# T02_noclock_rev1.net
KiCad netlist of a schematic drawn in EAGLE
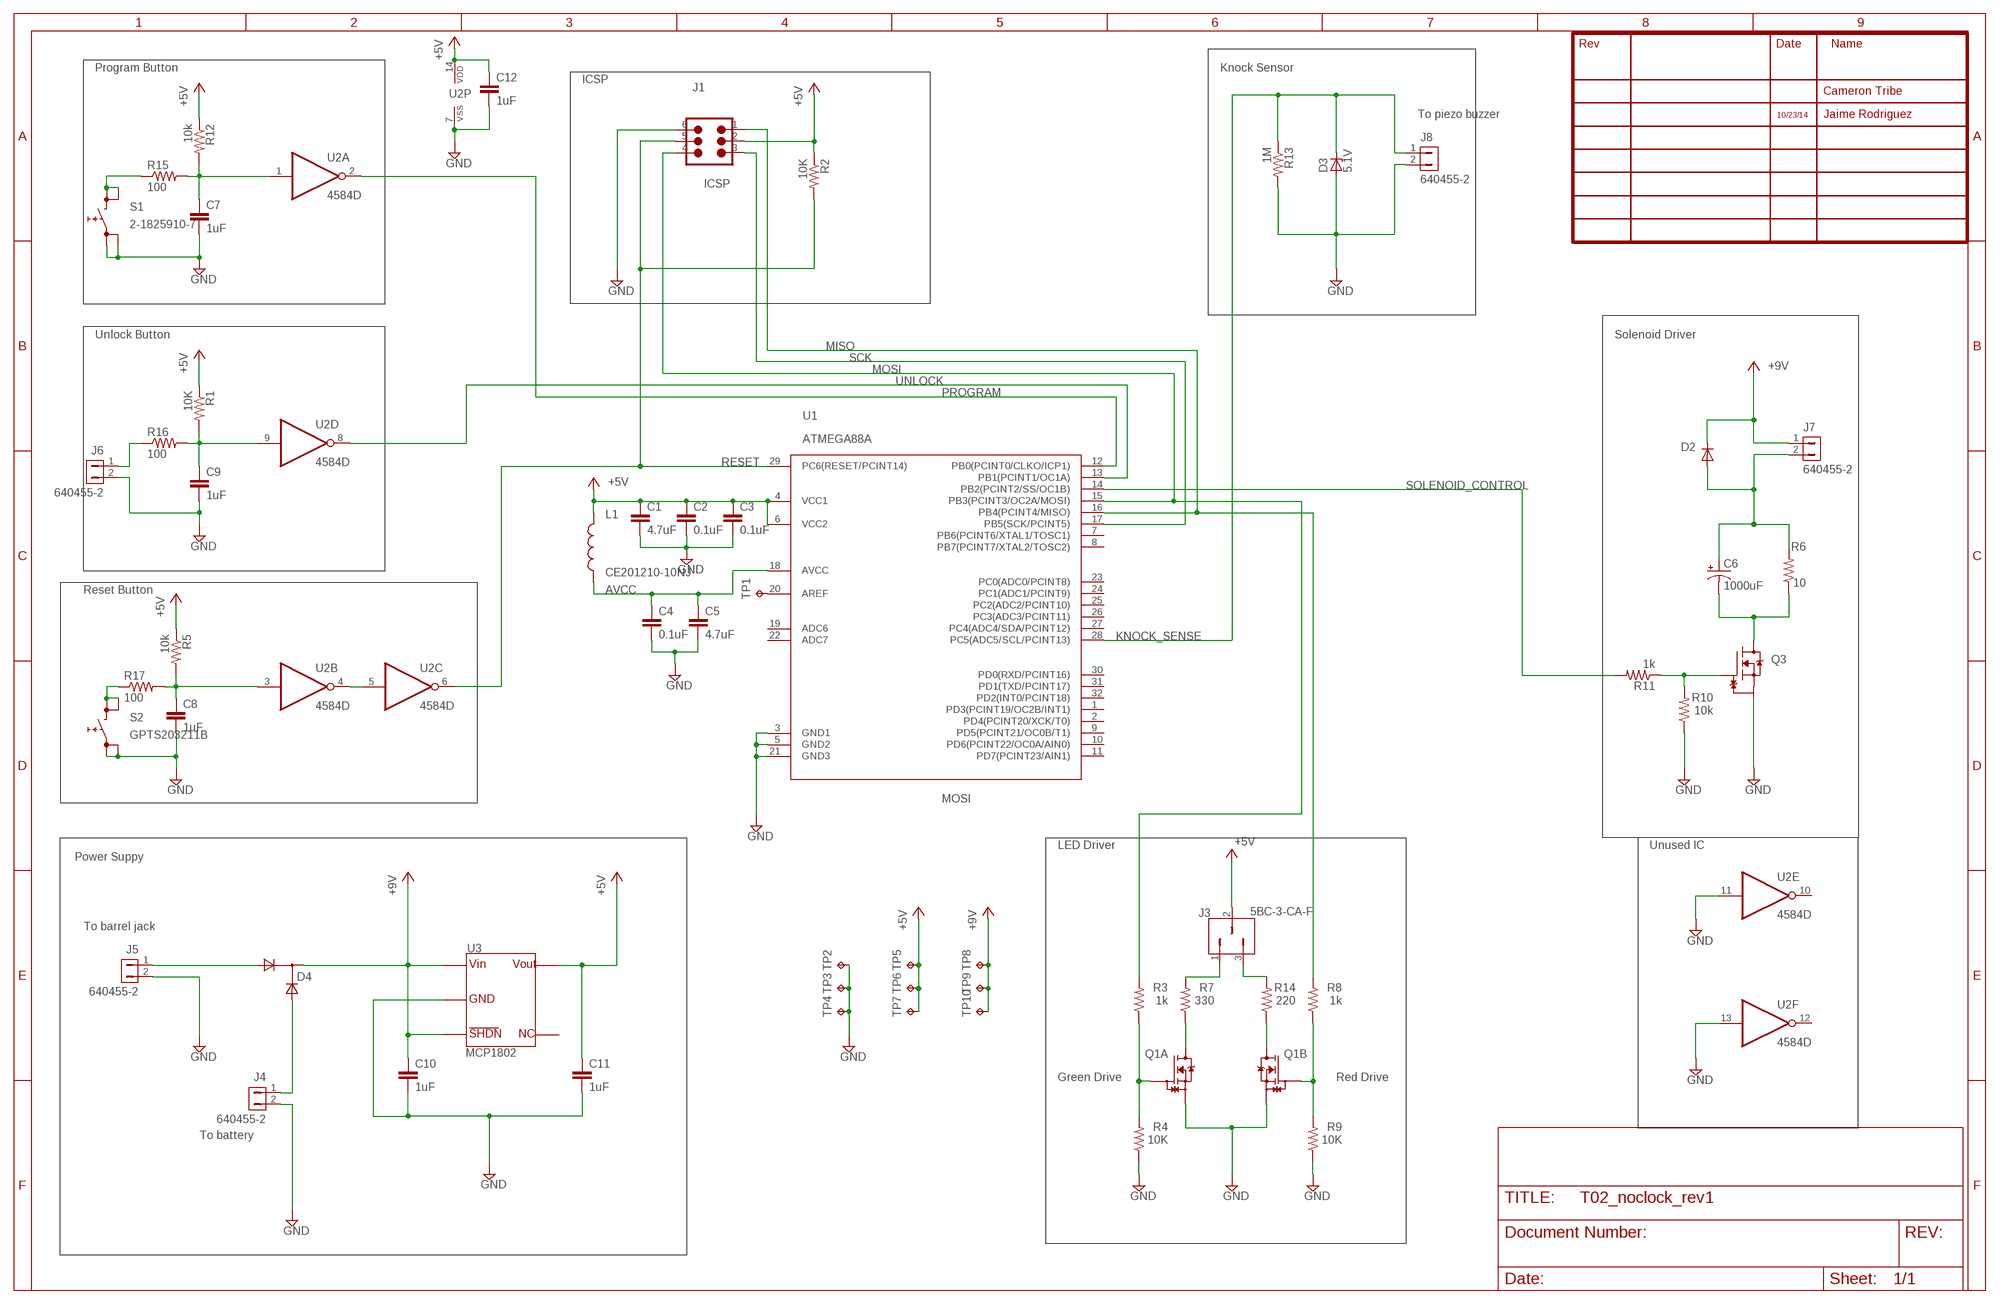
[diagram p0: schematic, sheet 1]

(export (version "E")
  (design (tool "Eeschema 10.0.6"))
  (components
    (comp (ref "C1")
      (value "4.7uF")
      (footprint "eagle-import:C0805")
      (fields (field (name "PARTNUM") "CL21A475KOFNNNE"))
      (libsource (lib "eagle-import") (part "C-EUC0805"))
    )
    (comp (ref "C2")
      (value "0.1uF")
      (footprint "eagle-import:C0805")
      (fields (field (name "PARTNUM") "GRM155R61A104KA01D"))
      (libsource (lib "eagle-import") (part "C-EUC0805"))
    )
    (comp (ref "C3")
      (value "0.1uF")
      (footprint "eagle-import:C0805")
      (fields (field (name "PARTNUM") "GRM155R61A104KA01D"))
      (libsource (lib "eagle-import") (part "C-EUC0805"))
    )
    (comp (ref "C4")
      (value "0.1uF")
      (footprint "eagle-import:C0805")
      (fields (field (name "PARTNUM") "GRM155R61A104KA01D"))
      (libsource (lib "eagle-import") (part "C-EUC0805"))
    )
    (comp (ref "C5")
      (value "4.7uF")
      (footprint "eagle-import:C0805")
      (fields (field (name "PARTNUM") "CL21A475KOFNNNE"))
      (libsource (lib "eagle-import") (part "C-EUC0805"))
    )
    (comp (ref "C6")
      (value "1000uF")
      (footprint "eagle-import:EKY-100ELL102MH20D")
      (libsource (lib "eagle-import") (part "EKY-100ELL102MH20D"))
    )
    (comp (ref "C7")
      (value "1uF")
      (footprint "eagle-import:C0805")
      (fields (field (name "PARTNUM") "CL21B105KBFNNNE"))
      (libsource (lib "eagle-import") (part "C-EUC0805"))
    )
    (comp (ref "C8")
      (value "1uF")
      (footprint "eagle-import:C0805")
      (fields (field (name "PARTNUM") "CL21B105KBFNNNE"))
      (libsource (lib "eagle-import") (part "C-EUC0805"))
    )
    (comp (ref "C9")
      (value "1uF")
      (footprint "eagle-import:C0805")
      (fields (field (name "PARTNUM") "CL21B105KBFNNNE"))
      (libsource (lib "eagle-import") (part "C-EUC0805"))
    )
    (comp (ref "C10")
      (value "1uF")
      (footprint "eagle-import:C0805")
      (fields (field (name "PARTNUM") "CL21B105KBFNNNE"))
      (libsource (lib "eagle-import") (part "C-EUC0805"))
    )
    (comp (ref "C11")
      (value "1uF")
      (footprint "eagle-import:C0805")
      (fields (field (name "PARTNUM") "CL21B105KBFNNNE"))
      (libsource (lib "eagle-import") (part "C-EUC0805"))
    )
    (comp (ref "C12")
      (value "1uF")
      (footprint "eagle-import:C0805")
      (fields (field (name "PARTNUM") "CL21B105KBFNNNE"))
      (libsource (lib "eagle-import") (part "C-EUC0805"))
    )
    (comp (ref "D2")
      (value "GF1")
      (footprint "eagle-import:SMA-DO214AC")
      (fields (field (name "PARTNUM") "S1J"))
      (libsource (lib "eagle-import") (part "GF1"))
    )
    (comp (ref "D3")
      (value "5.1V")
      (footprint "eagle-import:SOT23")
      (fields (field (name "PARTNUM") "BZX84C4V7-TP "))
      (libsource (lib "eagle-import") (part "ZENER-DIODESOT23"))
    )
    (comp (ref "D4")
      (value "PMEG2005CT,215")
      (footprint "eagle-import:SOT-23")
      (libsource (lib "eagle-import") (part "PMEG2005CT,215"))
    )
    (comp (ref "J1")
      (value "ICSP")
      (footprint "eagle-import:ICSP")
      (libsource (lib "eagle-import") (part "ICSP"))
    )
    (comp (ref "J3")
      (value "5BC-3-CA-F")
      (footprint "eagle-import:3_PIN_CONNECTOR")
      (libsource (lib "eagle-import") (part "5BC-3-CA-F"))
    )
    (comp (ref "J4")
      (value "640455-2")
      (footprint "eagle-import:2-PIN_CONNECTOR")
      (libsource (lib "eagle-import") (part "640455-2"))
    )
    (comp (ref "J5")
      (value "640455-2")
      (footprint "eagle-import:2-PIN_CONNECTOR")
      (libsource (lib "eagle-import") (part "640455-2"))
    )
    (comp (ref "J6")
      (value "640455-2")
      (footprint "eagle-import:2-PIN_CONNECTOR")
      (libsource (lib "eagle-import") (part "640455-2"))
    )
    (comp (ref "J7")
      (value "640455-2")
      (footprint "eagle-import:2-PIN_CONNECTOR")
      (libsource (lib "eagle-import") (part "640455-2"))
    )
    (comp (ref "J8")
      (value "640455-2")
      (footprint "eagle-import:2-PIN_CONNECTOR")
      (libsource (lib "eagle-import") (part "640455-2"))
    )
    (comp (ref "L1")
      (value "CE201210-10NJ")
      (footprint "eagle-import:R0805")
      (libsource (lib "eagle-import") (part "CE201210-10NJ"))
    )
    (comp (ref "Q1")
      (value "DMN63D8LDW-7")
      (footprint "eagle-import:SOT363")
      (fields (field (name "PARTNUM") "DMN63D8LDW-7"))
      (libsource (lib "eagle-import") (part "DMN63D8LDW-7"))
    )
    (comp (ref "Q3")
      (value "DMG1012UW-7")
      (footprint "eagle-import:SOT323")
      (libsource (lib "eagle-import") (part "DMG1012UW-7"))
    )
    (comp (ref "R1")
      (value "10K")
      (footprint "eagle-import:R0805")
      (fields (field (name "PARTNUM") "ESR10EZPJ103"))
      (libsource (lib "eagle-import") (part "R-US_R0805"))
    )
    (comp (ref "R2")
      (value "10K")
      (footprint "eagle-import:R0805")
      (fields (field (name "PARTNUM") "ESR10EZPJ103"))
      (libsource (lib "eagle-import") (part "R-US_R0805"))
    )
    (comp (ref "R3")
      (value "1k")
      (footprint "eagle-import:R0805")
      (fields (field (name "PARTNUM") "MCR10ERTF1001"))
      (libsource (lib "eagle-import") (part "R-US_R0805"))
    )
    (comp (ref "R4")
      (value "10K")
      (footprint "eagle-import:R0805")
      (fields (field (name "PARTNUM") "ESR10EZPJ103"))
      (libsource (lib "eagle-import") (part "R-US_R0805"))
    )
    (comp (ref "R5")
      (value "10k")
      (footprint "eagle-import:R0805")
      (fields (field (name "PARTNUM") "ESR10EZPJ103"))
      (libsource (lib "eagle-import") (part "R-US_R0805"))
    )
    (comp (ref "R6")
      (value "10")
      (footprint "eagle-import:R2512")
      (fields (field (name "PARTNUM") "CRM2512-JW-100ELF "))
      (libsource (lib "eagle-import") (part "R-US_R2512"))
    )
    (comp (ref "R7")
      (value "330")
      (footprint "eagle-import:R0805")
      (fields (field (name "PARTNUM") "MCR10ERTF3300"))
      (libsource (lib "eagle-import") (part "R-US_R0805"))
    )
    (comp (ref "R8")
      (value "1k")
      (footprint "eagle-import:R0805")
      (fields (field (name "PARTNUM") "MCR10ERTF1001"))
      (libsource (lib "eagle-import") (part "R-US_R0805"))
    )
    (comp (ref "R9")
      (value "10K")
      (footprint "eagle-import:R0805")
      (fields (field (name "PARTNUM") "ESR10EZPJ103"))
      (libsource (lib "eagle-import") (part "R-US_R0805"))
    )
    (comp (ref "R10")
      (value "10k")
      (footprint "eagle-import:R0805")
      (fields (field (name "PARTNUM") "ESR10EZPJ103"))
      (libsource (lib "eagle-import") (part "R-US_R0805"))
    )
    (comp (ref "R11")
      (value "1k")
      (footprint "eagle-import:R0805")
      (fields (field (name "PARTNUM") "MCR10ERTF1001"))
      (libsource (lib "eagle-import") (part "R-US_R0805"))
    )
    (comp (ref "R12")
      (value "10k")
      (footprint "eagle-import:R0805")
      (fields (field (name "PARTNUM") "ESR10EZPJ103"))
      (libsource (lib "eagle-import") (part "R-US_R0805"))
    )
    (comp (ref "R13")
      (value "1M")
      (footprint "eagle-import:R0805")
      (fields (field (name "PARTNUM") "RMCF0805JT1M00"))
      (libsource (lib "eagle-import") (part "R-US_R0805"))
    )
    (comp (ref "R14")
      (value "220")
      (footprint "eagle-import:R0805")
      (fields (field (name "PARTNUM") "RMCF0805FT220R"))
      (libsource (lib "eagle-import") (part "R-US_R0805"))
    )
    (comp (ref "R15")
      (value "100")
      (footprint "eagle-import:R0805")
      (fields (field (name "PARTNUM") "ESR10EZPJ103"))
      (libsource (lib "eagle-import") (part "R-US_R0805"))
    )
    (comp (ref "R16")
      (value "100")
      (footprint "eagle-import:R0805")
      (fields (field (name "PARTNUM") "ESR10EZPJ103"))
      (libsource (lib "eagle-import") (part "R-US_R0805"))
    )
    (comp (ref "R17")
      (value "100")
      (footprint "eagle-import:R0805")
      (fields (field (name "PARTNUM") "ESR10EZPJ103"))
      (libsource (lib "eagle-import") (part "R-US_R0805"))
    )
    (comp (ref "S1")
      (value "2-1825910-7")
      (footprint "eagle-import:FSM14JH")
      (libsource (lib "eagle-import") (part "2-1825910-7"))
    )
    (comp (ref "S2")
      (value "GPTS203211B")
      (footprint "eagle-import:GPTS203211B")
      (libsource (lib "eagle-import") (part "GPTS203211B"))
    )
    (comp (ref "TP1")
      (value "TPTP19R")
      (footprint "eagle-import:TP19R")
      (libsource (lib "eagle-import") (part "TPTP19R"))
    )
    (comp (ref "TP2")
      (value "TPTP19R")
      (footprint "eagle-import:TP19R")
      (libsource (lib "eagle-import") (part "TPTP19R"))
    )
    (comp (ref "TP3")
      (value "TPTP19R")
      (footprint "eagle-import:TP19R")
      (libsource (lib "eagle-import") (part "TPTP19R"))
    )
    (comp (ref "TP4")
      (value "TPTP19R")
      (footprint "eagle-import:TP19R")
      (libsource (lib "eagle-import") (part "TPTP19R"))
    )
    (comp (ref "TP5")
      (value "TPTP19R")
      (footprint "eagle-import:TP19R")
      (libsource (lib "eagle-import") (part "TPTP19R"))
    )
    (comp (ref "TP6")
      (value "TPTP19R")
      (footprint "eagle-import:TP19R")
      (libsource (lib "eagle-import") (part "TPTP19R"))
    )
    (comp (ref "TP7")
      (value "TPTP19R")
      (footprint "eagle-import:TP19R")
      (libsource (lib "eagle-import") (part "TPTP19R"))
    )
    (comp (ref "TP8")
      (value "TPTP19R")
      (footprint "eagle-import:TP19R")
      (libsource (lib "eagle-import") (part "TPTP19R"))
    )
    (comp (ref "TP9")
      (value "TPTP19R")
      (footprint "eagle-import:TP19R")
      (libsource (lib "eagle-import") (part "TPTP19R"))
    )
    (comp (ref "TP10")
      (value "TPTP19R")
      (footprint "eagle-import:TP19R")
      (libsource (lib "eagle-import") (part "TPTP19R"))
    )
    (comp (ref "U1")
      (value "ATMEGA88A")
      (footprint "eagle-import:TQFP32")
      (fields (field (name "PARTNUM") "ATMEGA88A-AUR "))
      (libsource (lib "eagle-import") (part "ATMEGA88A"))
    )
    (comp (ref "U2")
      (value "4584D")
      (footprint "eagle-import:SO14")
      (fields (field (name "PARTNUM") "4584D"))
      (libsource (lib "eagle-import") (part "4584D"))
    )
    (comp (ref "U3")
      (value "MCP1802")
      (footprint "eagle-import:SOT23-5")
      (libsource (lib "eagle-import") (part "MCP1802"))
    )
  )
  (nets
    (net (code "1") (name "+5V") (class "Default")
      (node (ref "C1") (pin "1") (pinfunction "1_1") (pintype "passive"))
      (node (ref "C11") (pin "1") (pinfunction "1_1") (pintype "passive"))
      (node (ref "C12") (pin "1") (pinfunction "1_1") (pintype "passive"))
      (node (ref "C2") (pin "1") (pinfunction "1_1") (pintype "passive"))
      (node (ref "C3") (pin "1") (pinfunction "1_1") (pintype "passive"))
      (node (ref "J1") (pin "2") (pinfunction "2_2") (pintype "passive"))
      (node (ref "J3") (pin "2") (pinfunction "2_2") (pintype "passive"))
      (node (ref "L1") (pin "2") (pinfunction "2_2") (pintype "passive"))
      (node (ref "R1") (pin "1") (pinfunction "1_1") (pintype "passive"))
      (node (ref "R12") (pin "1") (pinfunction "1_1") (pintype "passive"))
      (node (ref "R2") (pin "1") (pinfunction "1_1") (pintype "passive"))
      (node (ref "R5") (pin "1") (pinfunction "1_1") (pintype "passive"))
      (node (ref "TP5") (pin "TP") (pinfunction "TP_TP") (pintype "input"))
      (node (ref "TP6") (pin "TP") (pinfunction "TP_TP") (pintype "input"))
      (node (ref "TP7") (pin "TP") (pinfunction "TP_TP") (pintype "input"))
      (node (ref "U1") (pin "4") (pinfunction "VCC1_4") (pintype "power_in"))
      (node (ref "U1") (pin "6") (pinfunction "VCC2_6") (pintype "passive"))
      (node (ref "U2") (pin "14") (pinfunction "VDD_14") (pintype "power_in"))
      (node (ref "U3") (pin "5") (pinfunction "VOUT_5") (pintype "passive"))
    )
    (net (code "2") (name "+9V") (class "Default")
      (node (ref "C10") (pin "1") (pinfunction "1_1") (pintype "passive"))
      (node (ref "D2") (pin "K") (pinfunction "C_K") (pintype "passive"))
      (node (ref "D4") (pin "2") (pinfunction "C_2") (pintype "passive"))
      (node (ref "J7") (pin "1") (pinfunction "1_1") (pintype "passive"))
      (node (ref "TP10") (pin "TP") (pinfunction "TP_TP") (pintype "input"))
      (node (ref "TP8") (pin "TP") (pinfunction "TP_TP") (pintype "input"))
      (node (ref "TP9") (pin "TP") (pinfunction "TP_TP") (pintype "input"))
      (node (ref "U3") (pin "1") (pinfunction "VIN_1") (pintype "passive"))
      (node (ref "U3") (pin "3") (pinfunction "SHDN_3") (pintype "passive"))
    )
    (net (code "3") (name "/AVCC") (class "Default")
      (node (ref "C4") (pin "1") (pinfunction "1_1") (pintype "passive"))
      (node (ref "C5") (pin "1") (pinfunction "1_1") (pintype "passive"))
      (node (ref "L1") (pin "1") (pinfunction "1_1") (pintype "passive"))
      (node (ref "U1") (pin "18") (pinfunction "AVCC_18") (pintype "power_in"))
    )
    (net (code "4") (name "/KNOCK_SENSE") (class "Default")
      (node (ref "D3") (pin "3") (pinfunction "C_3") (pintype "passive"))
      (node (ref "J8") (pin "1") (pinfunction "1_1") (pintype "passive"))
      (node (ref "R13") (pin "1") (pinfunction "1_1") (pintype "passive"))
      (node (ref "U1") (pin "28") (pinfunction "PC5(ADC5/SCL/PCINT13)_28") (pintype "bidirectional"))
    )
    (net (code "5") (name "/MISO") (class "Default")
      (node (ref "J1") (pin "1") (pinfunction "1_1") (pintype "passive"))
      (node (ref "R8") (pin "2") (pinfunction "2_2") (pintype "passive"))
      (node (ref "U1") (pin "16") (pinfunction "PB4(PCINT4/MISO)_16") (pintype "bidirectional"))
    )
    (net (code "6") (name "/MOSI") (class "Default")
      (node (ref "J1") (pin "4") (pinfunction "4_4") (pintype "passive"))
      (node (ref "R3") (pin "2") (pinfunction "2_2") (pintype "passive"))
      (node (ref "U1") (pin "15") (pinfunction "PB3(PCINT3/OC2A/MOSI)_15") (pintype "bidirectional"))
    )
    (net (code "7") (name "/PROGRAM") (class "Default")
      (node (ref "U1") (pin "12") (pinfunction "PB0(PCINT0/CLKO/ICP1)_12") (pintype "bidirectional"))
      (node (ref "U2") (pin "2") (pinfunction "O_2") (pintype "output"))
    )
    (net (code "8") (name "/RESET") (class "Default")
      (node (ref "J1") (pin "5") (pinfunction "5_5") (pintype "passive"))
      (node (ref "R2") (pin "2") (pinfunction "2_2") (pintype "passive"))
      (node (ref "U1") (pin "29") (pinfunction "PC6(RESET/PCINT14)_29") (pintype "bidirectional"))
      (node (ref "U2") (pin "6") (pinfunction "O_6") (pintype "output"))
    )
    (net (code "9") (name "/SCK") (class "Default")
      (node (ref "J1") (pin "3") (pinfunction "3_3") (pintype "passive"))
      (node (ref "U1") (pin "17") (pinfunction "PB5(SCK/PCINT5)_17") (pintype "bidirectional"))
    )
    (net (code "10") (name "/SOLENOID_CONTROL") (class "Default")
      (node (ref "R11") (pin "2") (pinfunction "2_2") (pintype "passive"))
      (node (ref "U1") (pin "14") (pinfunction "PB2(PCINT2/SS/OC1B)_14") (pintype "bidirectional"))
    )
    (net (code "11") (name "/UNLOCK") (class "Default")
      (node (ref "U1") (pin "13") (pinfunction "PB1(PCINT1/OC1A)_13") (pintype "bidirectional"))
      (node (ref "U2") (pin "8") (pinfunction "O_8") (pintype "output"))
    )
    (net (code "12") (name "GND") (class "Default")
      (node (ref "C1") (pin "2") (pinfunction "2_2") (pintype "passive"))
      (node (ref "C10") (pin "2") (pinfunction "2_2") (pintype "passive"))
      (node (ref "C11") (pin "2") (pinfunction "2_2") (pintype "passive"))
      (node (ref "C12") (pin "2") (pinfunction "2_2") (pintype "passive"))
      (node (ref "C2") (pin "2") (pinfunction "2_2") (pintype "passive"))
      (node (ref "C3") (pin "2") (pinfunction "2_2") (pintype "passive"))
      (node (ref "C4") (pin "2") (pinfunction "2_2") (pintype "passive"))
      (node (ref "C5") (pin "2") (pinfunction "2_2") (pintype "passive"))
      (node (ref "C7") (pin "2") (pinfunction "2_2") (pintype "passive"))
      (node (ref "C8") (pin "2") (pinfunction "2_2") (pintype "passive"))
      (node (ref "C9") (pin "2") (pinfunction "2_2") (pintype "passive"))
      (node (ref "D3") (pin "1") (pinfunction "A_1") (pintype "passive"))
      (node (ref "J1") (pin "6") (pinfunction "6_6") (pintype "passive"))
      (node (ref "J4") (pin "2") (pinfunction "2_2") (pintype "passive"))
      (node (ref "J5") (pin "2") (pinfunction "2_2") (pintype "passive"))
      (node (ref "J6") (pin "2") (pinfunction "2_2") (pintype "passive"))
      (node (ref "J8") (pin "2") (pinfunction "2_2") (pintype "passive"))
      (node (ref "Q1") (pin "S1") (pinfunction "S_S1") (pintype "passive"))
      (node (ref "Q1") (pin "S2") (pinfunction "S_S2") (pintype "passive"))
      (node (ref "Q3") (pin "3") (pinfunction "S_3") (pintype "passive"))
      (node (ref "R10") (pin "1") (pinfunction "1_1") (pintype "passive"))
      (node (ref "R13") (pin "2") (pinfunction "2_2") (pintype "passive"))
      (node (ref "R4") (pin "1") (pinfunction "1_1") (pintype "passive"))
      (node (ref "R9") (pin "1") (pinfunction "1_1") (pintype "passive"))
      (node (ref "S1") (pin "1") (pinfunction "1_1") (pintype "passive"))
      (node (ref "S1") (pin "2") (pinfunction "2_2") (pintype "passive"))
      (node (ref "S2") (pin "1") (pinfunction "1_1") (pintype "passive"))
      (node (ref "S2") (pin "2") (pinfunction "2_2") (pintype "passive"))
      (node (ref "TP2") (pin "TP") (pinfunction "TP_TP") (pintype "input"))
      (node (ref "TP3") (pin "TP") (pinfunction "TP_TP") (pintype "input"))
      (node (ref "TP4") (pin "TP") (pinfunction "TP_TP") (pintype "input"))
      (node (ref "U1") (pin "21") (pinfunction "GND3_21") (pintype "power_in"))
      (node (ref "U1") (pin "3") (pinfunction "GND1_3") (pintype "power_in"))
      (node (ref "U1") (pin "5") (pinfunction "GND2_5") (pintype "power_in"))
      (node (ref "U2") (pin "11") (pinfunction "I_11") (pintype "input"))
      (node (ref "U2") (pin "13") (pinfunction "I_13") (pintype "input"))
      (node (ref "U2") (pin "7") (pinfunction "VSS_7") (pintype "power_in"))
      (node (ref "U3") (pin "2") (pinfunction "GND_2") (pintype "power_in"))
    )
    (net (code "13") (name "Net-(C6-Pad+)") (class "Default")
      (node (ref "C6") (pin "+") (pinfunction "+_+") (pintype "passive"))
      (node (ref "D2") (pin "A") (pinfunction "A_A") (pintype "passive"))
      (node (ref "J7") (pin "2") (pinfunction "2_2") (pintype "passive"))
      (node (ref "R6") (pin "2") (pinfunction "2_2") (pintype "passive"))
    )
    (net (code "14") (name "Net-(D4-A1)") (class "Default")
      (node (ref "D4") (pin "3") (pinfunction "A1_3") (pintype "passive"))
      (node (ref "J5") (pin "1") (pinfunction "1_1") (pintype "passive"))
    )
    (net (code "15") (name "Net-(D4-A2)") (class "Default")
      (node (ref "D4") (pin "1") (pinfunction "A2_1") (pintype "passive"))
      (node (ref "J4") (pin "1") (pinfunction "1_1") (pintype "passive"))
    )
    (net (code "16") (name "Net-(J3-Pad1)") (class "Default")
      (node (ref "J3") (pin "1") (pinfunction "1_1") (pintype "passive"))
      (node (ref "R7") (pin "2") (pinfunction "2_2") (pintype "passive"))
    )
    (net (code "17") (name "Net-(J3-Pad3)") (class "Default")
      (node (ref "J3") (pin "3") (pinfunction "3_3") (pintype "passive"))
      (node (ref "R14") (pin "2") (pinfunction "2_2") (pintype "passive"))
    )
    (net (code "18") (name "Net-(J6-Pad1)") (class "Default")
      (node (ref "J6") (pin "1") (pinfunction "1_1") (pintype "passive"))
      (node (ref "R16") (pin "1") (pinfunction "1_1") (pintype "passive"))
    )
    (net (code "19") (name "Net-(Q1A-D)") (class "Default")
      (node (ref "Q1") (pin "D1") (pinfunction "D_D1") (pintype "passive"))
      (node (ref "R7") (pin "1") (pinfunction "1_1") (pintype "passive"))
    )
    (net (code "20") (name "Net-(Q1A-G)") (class "Default")
      (node (ref "Q1") (pin "G1") (pinfunction "G_G1") (pintype "passive"))
      (node (ref "R3") (pin "1") (pinfunction "1_1") (pintype "passive"))
      (node (ref "R4") (pin "2") (pinfunction "2_2") (pintype "passive"))
    )
    (net (code "21") (name "Net-(Q1B-D)") (class "Default")
      (node (ref "Q1") (pin "D2") (pinfunction "D_D2") (pintype "passive"))
      (node (ref "R14") (pin "1") (pinfunction "1_1") (pintype "passive"))
    )
    (net (code "22") (name "Net-(Q1B-G)") (class "Default")
      (node (ref "Q1") (pin "G2") (pinfunction "G_G2") (pintype "passive"))
      (node (ref "R8") (pin "1") (pinfunction "1_1") (pintype "passive"))
      (node (ref "R9") (pin "2") (pinfunction "2_2") (pintype "passive"))
    )
    (net (code "23") (name "Net-(Q3-D)") (class "Default")
      (node (ref "C6") (pin "-") (pinfunction "-_-") (pintype "passive"))
      (node (ref "Q3") (pin "1") (pinfunction "D_1") (pintype "passive"))
      (node (ref "R6") (pin "1") (pinfunction "1_1") (pintype "passive"))
    )
    (net (code "24") (name "Net-(Q3-G)") (class "Default")
      (node (ref "Q3") (pin "2") (pinfunction "G_2") (pintype "passive"))
      (node (ref "R10") (pin "2") (pinfunction "2_2") (pintype "passive"))
      (node (ref "R11") (pin "1") (pinfunction "1_1") (pintype "passive"))
    )
    (net (code "25") (name "Net-(R15-Pad1)") (class "Default")
      (node (ref "R15") (pin "1") (pinfunction "1_1") (pintype "passive"))
      (node (ref "S1") (pin "3") (pinfunction "3_3") (pintype "passive"))
      (node (ref "S1") (pin "4") (pinfunction "4_4") (pintype "passive"))
    )
    (net (code "26") (name "Net-(R17-Pad1)") (class "Default")
      (node (ref "R17") (pin "1") (pinfunction "1_1") (pintype "passive"))
      (node (ref "S2") (pin "3") (pinfunction "3_3") (pintype "passive"))
      (node (ref "S2") (pin "4") (pinfunction "4_4") (pintype "passive"))
    )
    (net (code "27") (name "Net-(U1-AREF)") (class "Default")
      (node (ref "TP1") (pin "TP") (pinfunction "TP_TP") (pintype "input"))
      (node (ref "U1") (pin "20") (pinfunction "AREF_20") (pintype "power_in"))
    )
    (net (code "28") (name "Net-(U2A-I)") (class "Default")
      (node (ref "C7") (pin "1") (pinfunction "1_1") (pintype "passive"))
      (node (ref "R12") (pin "2") (pinfunction "2_2") (pintype "passive"))
      (node (ref "R15") (pin "2") (pinfunction "2_2") (pintype "passive"))
      (node (ref "U2") (pin "1") (pinfunction "I_1") (pintype "input"))
    )
    (net (code "29") (name "Net-(U2B-I)") (class "Default")
      (node (ref "C8") (pin "1") (pinfunction "1_1") (pintype "passive"))
      (node (ref "R17") (pin "2") (pinfunction "2_2") (pintype "passive"))
      (node (ref "R5") (pin "2") (pinfunction "2_2") (pintype "passive"))
      (node (ref "U2") (pin "3") (pinfunction "I_3") (pintype "input"))
    )
    (net (code "30") (name "Net-(U2B-O)") (class "Default")
      (node (ref "U2") (pin "4") (pinfunction "O_4") (pintype "output"))
      (node (ref "U2") (pin "5") (pinfunction "I_5") (pintype "input"))
    )
    (net (code "31") (name "Net-(U2D-I)") (class "Default")
      (node (ref "C9") (pin "1") (pinfunction "1_1") (pintype "passive"))
      (node (ref "R1") (pin "2") (pinfunction "2_2") (pintype "passive"))
      (node (ref "R16") (pin "2") (pinfunction "2_2") (pintype "passive"))
      (node (ref "U2") (pin "9") (pinfunction "I_9") (pintype "input"))
    )
    (net (code "32") (name "unconnected-(U1-ADC6-Pad19)") (class "Default")
      (node (ref "U1") (pin "19") (pinfunction "ADC6_19") (pintype "bidirectional"))
    )
    (net (code "33") (name "unconnected-(U1-ADC7-Pad22)") (class "Default")
      (node (ref "U1") (pin "22") (pinfunction "ADC7_22") (pintype "bidirectional"))
    )
    (net (code "34") (name "unconnected-(U1-PB6(PCINT6{slash}XTAL1{slash}TOSC1)-Pad7)") (class "Default")
      (node (ref "U1") (pin "7") (pinfunction "PB6(PCINT6/XTAL1/TOSC1)_7") (pintype "bidirectional"))
    )
    (net (code "35") (name "unconnected-(U1-PB7(PCINT7{slash}XTAL2{slash}TOSC2)-Pad8)") (class "Default")
      (node (ref "U1") (pin "8") (pinfunction "PB7(PCINT7/XTAL2/TOSC2)_8") (pintype "bidirectional"))
    )
    (net (code "36") (name "unconnected-(U1-PC0(ADC0{slash}PCINT8)-Pad23)") (class "Default")
      (node (ref "U1") (pin "23") (pinfunction "PC0(ADC0/PCINT8)_23") (pintype "bidirectional"))
    )
    (net (code "37") (name "unconnected-(U1-PC1(ADC1{slash}PCINT9)-Pad24)") (class "Default")
      (node (ref "U1") (pin "24") (pinfunction "PC1(ADC1/PCINT9)_24") (pintype "bidirectional"))
    )
    (net (code "38") (name "unconnected-(U1-PC2(ADC2{slash}PCINT10)-Pad25)") (class "Default")
      (node (ref "U1") (pin "25") (pinfunction "PC2(ADC2/PCINT10)_25") (pintype "bidirectional"))
    )
    (net (code "39") (name "unconnected-(U1-PC3(ADC3{slash}PCINT11)-Pad26)") (class "Default")
      (node (ref "U1") (pin "26") (pinfunction "PC3(ADC3/PCINT11)_26") (pintype "bidirectional"))
    )
    (net (code "40") (name "unconnected-(U1-PC4(ADC4{slash}SDA{slash}PCINT12)-Pad27)") (class "Default")
      (node (ref "U1") (pin "27") (pinfunction "PC4(ADC4/SDA/PCINT12)_27") (pintype "bidirectional"))
    )
    (net (code "41") (name "unconnected-(U1-PD0(RXD{slash}PCINT16)-Pad30)") (class "Default")
      (node (ref "U1") (pin "30") (pinfunction "PD0(RXD/PCINT16)_30") (pintype "bidirectional"))
    )
    (net (code "42") (name "unconnected-(U1-PD1(TXD{slash}PCINT17)-Pad31)") (class "Default")
      (node (ref "U1") (pin "31") (pinfunction "PD1(TXD/PCINT17)_31") (pintype "bidirectional"))
    )
    (net (code "43") (name "unconnected-(U1-PD2(INT0{slash}PCINT18)-Pad32)") (class "Default")
      (node (ref "U1") (pin "32") (pinfunction "PD2(INT0/PCINT18)_32") (pintype "bidirectional"))
    )
    (net (code "44") (name "unconnected-(U1-PD3(PCINT19{slash}OC2B{slash}INT1)-Pad1)") (class "Default")
      (node (ref "U1") (pin "1") (pinfunction "PD3(PCINT19/OC2B/INT1)_1") (pintype "bidirectional"))
    )
    (net (code "45") (name "unconnected-(U1-PD4(PCINT20{slash}XCK{slash}T0)-Pad2)") (class "Default")
      (node (ref "U1") (pin "2") (pinfunction "PD4(PCINT20/XCK/T0)_2") (pintype "bidirectional"))
    )
    (net (code "46") (name "unconnected-(U1-PD5(PCINT21{slash}OC0B{slash}T1)-Pad9)") (class "Default")
      (node (ref "U1") (pin "9") (pinfunction "PD5(PCINT21/OC0B/T1)_9") (pintype "bidirectional"))
    )
    (net (code "47") (name "unconnected-(U1-PD6(PCINT22{slash}OC0A{slash}AIN0)-Pad10)") (class "Default")
      (node (ref "U1") (pin "10") (pinfunction "PD6(PCINT22/OC0A/AIN0)_10") (pintype "bidirectional"))
    )
    (net (code "48") (name "unconnected-(U1-PD7(PCINT23{slash}AIN1)-Pad11)") (class "Default")
      (node (ref "U1") (pin "11") (pinfunction "PD7(PCINT23/AIN1)_11") (pintype "bidirectional"))
    )
    (net (code "49") (name "unconnected-(U2E-O-Pad10)") (class "Default")
      (node (ref "U2") (pin "10") (pinfunction "O_10") (pintype "output"))
    )
    (net (code "50") (name "unconnected-(U2F-O-Pad12)") (class "Default")
      (node (ref "U2") (pin "12") (pinfunction "O_12") (pintype "output"))
    )
    (net (code "51") (name "unconnected-(U3-NC-Pad4)") (class "Default")
      (node (ref "U3") (pin "4") (pinfunction "NC_4") (pintype "no_connect"))
    )
  )
)
